# Controller_Board_Interface.net
KiCad netlist of a schematic drawn in Altium Designer
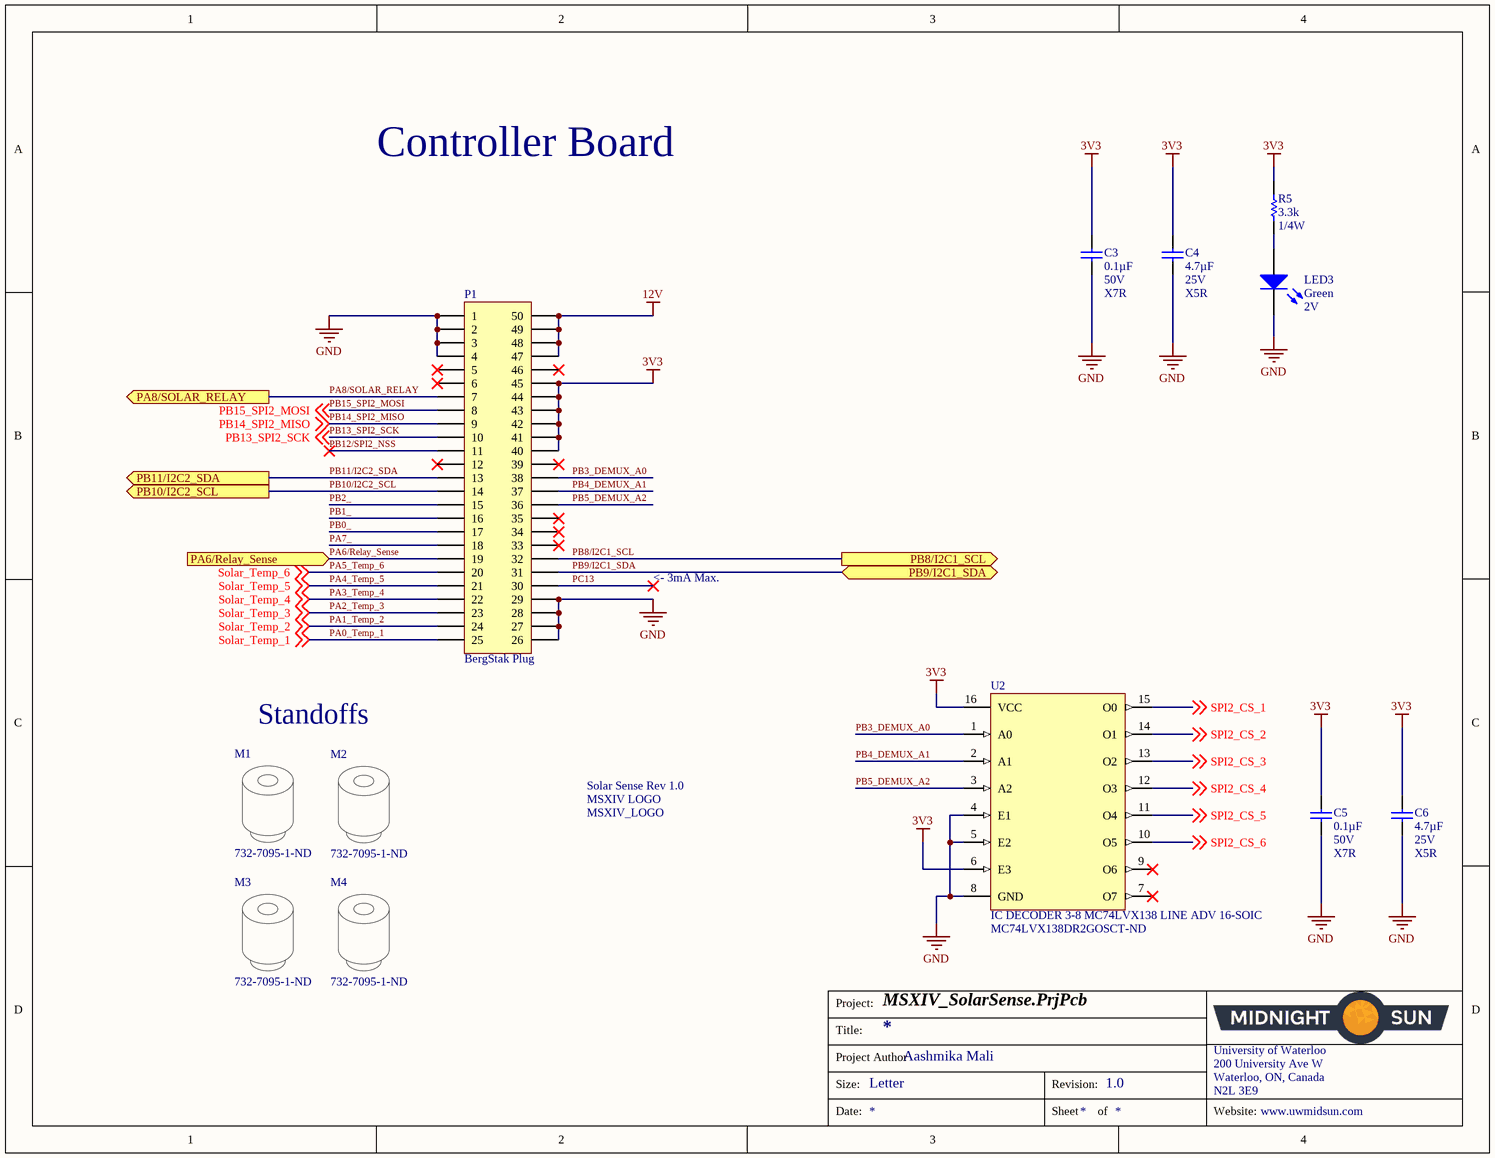
[diagram p0: Controller_Board_Interface.SchDoc]

(export (version "E")
  (design (tool "Eeschema 10.0.6"))
  (components
    (comp (ref "C3")
      (value "CAP CER 0.1UF 50V 10% X7R 0603")
      (footprint "CAP, 0603")
      (description "0.10µF ±10% 50V Ceramic Capacitor X7R 0603 (1608 Metric)")
      (fields
        (field (name "TOLERANCE") "±10%")
        (field (name "CAPACITANCE") "0.1µF")
        (field (name "VOLTAGE") "50V")
        (field (name "TEMPERATURE COEFFICIENT") "X7R")
      )
      (libsource (lib "Schematic Diagrams") (part "CAP CER 0.1UF 50V 10% X7R 0603"))
    )
    (comp (ref "C4")
      (value "CAP CER 4.7UF 25V 10% X5R 0603")
      (footprint "CAP, 0603")
      (description "4.7µF ±10% 25V Ceramic Capacitor X5R 0603 (1608 Metric)")
      (fields
        (field (name "TOLERANCE") "±10%")
        (field (name "CAPACITANCE") "4.7µF")
        (field (name "VOLTAGE") "25V")
        (field (name "TEMPERATURE COEFFICIENT") "X5R")
      )
      (libsource (lib "Schematic Diagrams") (part "CAP CER 4.7UF 25V 10% X5R 0603"))
    )
    (comp (ref "C5")
      (value "CAP CER 0.1UF 50V 10% X7R 0603")
      (footprint "CAP, 0603")
      (description "0.10µF ±10% 50V Ceramic Capacitor X7R 0603 (1608 Metric)")
      (fields
        (field (name "TOLERANCE") "±10%")
        (field (name "CAPACITANCE") "0.1µF")
        (field (name "VOLTAGE") "50V")
        (field (name "TEMPERATURE COEFFICIENT") "X7R")
      )
      (libsource (lib "Schematic Diagrams") (part "CAP CER 0.1UF 50V 10% X7R 0603"))
    )
    (comp (ref "C6")
      (value "CAP CER 4.7UF 25V 10% X5R 0603")
      (footprint "CAP, 0603")
      (description "4.7µF ±10% 25V Ceramic Capacitor X5R 0603 (1608 Metric)")
      (fields
        (field (name "TOLERANCE") "±10%")
        (field (name "CAPACITANCE") "4.7µF")
        (field (name "VOLTAGE") "25V")
        (field (name "TEMPERATURE COEFFICIENT") "X5R")
      )
      (libsource (lib "Schematic Diagrams") (part "CAP CER 4.7UF 25V 10% X5R 0603"))
    )
    (comp (ref "LED3")
      (value "LED GREEN CLEAR 2V 0603")
      (footprint "LED_0603")
      (description "Green 572nm LED Indication - Discrete 2V 0603 (1608 Metric)")
      (fields
        (field (name "MANUFACTURER") "Wurth Electronics Inc.")
        (field (name "MANUFACTURER PART NUMBER") "150060VS75000")
        (field (name "COLOR") "Green")
        (field (name "VOLTAGE - FORWARD (VF) (TYP)") "2V")
      )
      (libsource (lib "Schematic Diagrams") (part "LED GREEN CLEAR 2V 0603"))
    )
    (comp (ref "M1")
      (value "STANDOFF RND M2.5X0.45 STEEL 5MM")
      (footprint "M2.5 Standoff")
      (fields
        (field (name "MANUFACTURER") "Wurth Electronics")
        (field (name "MANUFACTURER PART NUMBER") "9774050151R")
        (field (name "SUPPLIER PART NUMBER 1") "732-7095-1-ND")
      )
      (libsource (lib "Schematic Diagrams") (part "STANDOFF RND M2.5X0.45 STEEL 5MM"))
    )
    (comp (ref "M2")
      (value "STANDOFF RND M2.5X0.45 STEEL 5MM")
      (footprint "M2.5 Standoff")
      (fields
        (field (name "MANUFACTURER") "Wurth Electronics")
        (field (name "MANUFACTURER PART NUMBER") "9774050151R")
        (field (name "SUPPLIER PART NUMBER 1") "732-7095-1-ND")
      )
      (libsource (lib "Schematic Diagrams") (part "STANDOFF RND M2.5X0.45 STEEL 5MM"))
    )
    (comp (ref "M3")
      (value "STANDOFF RND M2.5X0.45 STEEL 5MM")
      (footprint "M2.5 Standoff")
      (fields
        (field (name "MANUFACTURER") "Wurth Electronics")
        (field (name "MANUFACTURER PART NUMBER") "9774050151R")
        (field (name "SUPPLIER PART NUMBER 1") "732-7095-1-ND")
      )
      (libsource (lib "Schematic Diagrams") (part "STANDOFF RND M2.5X0.45 STEEL 5MM"))
    )
    (comp (ref "M4")
      (value "STANDOFF RND M2.5X0.45 STEEL 5MM")
      (footprint "M2.5 Standoff")
      (fields
        (field (name "MANUFACTURER") "Wurth Electronics")
        (field (name "MANUFACTURER PART NUMBER") "9774050151R")
        (field (name "SUPPLIER PART NUMBER 1") "732-7095-1-ND")
      )
      (libsource (lib "Schematic Diagrams") (part "STANDOFF RND M2.5X0.45 STEEL 5MM"))
    )
    (comp (ref "P1")
      (value "CONN 50POS Bergstak Plug 0.02\"")
      (footprint "CONN, Bergstak 50 Pos Plug")
      (description "50 Position Connector Plug, Outer Shroud Contacts Surface Mount Gold")
      (fields (field (name "SERIES") "BergStak Plug"))
      (libsource (lib "Schematic Diagrams") (part "CONN 50POS Bergstak Plug 0.02{dblquote}"))
    )
    (comp (ref "R5")
      (value "RES 3.3K OHM 1% 1/4W 0603")
      (footprint "RES, 0603")
      (fields
        (field (name "TOLERANCE") "±1%")
        (field (name "RESISTANCE") "3.3k")
        (field (name "POWER") "1/4W")
      )
      (libsource (lib "Schematic Diagrams") (part "RES 3.3K OHM 1% 1/4W 0603"))
    )
    (comp (ref "Solar Sense Rev 1.0")
      (value "MSXIV_LOGO")
      (footprint "MSXIV LOGO")
      (libsource (lib "Schematic Diagrams") (part "MSXIV_LOGO"))
    )
    (comp (ref "U2")
      (value "IC DECODER 3-8 MC74LVX138 LINE ADV 16-SOIC")
      (footprint "SOIC-16 CASE 751B-05 ISSUE K MC74LVX138")
      (description "Decoder/Demultiplexer 1 x 3:8 16-SOIC")
      (fields
        (field (name "MANUFACTURER") "ON Semiconductor")
        (field (name "MANUFACTURER PART NUMBER") "MC74LVX138DR2G")
        (field (name "SUPPLIER PART NUMBER 1") "MC74LVX138DR2GOSCT-ND")
      )
      (libsource (lib "Schematic Diagrams") (part "IC DECODER 3-8 MC74LVX138 LINE ADV 16-SOIC"))
    )
  )
  (nets
    (net (code "1") (name "/PA6{slash}Relay_Sense") (class "Default")
      (node (ref "P1") (pin "19") (pinfunction "19_19") (pintype "passive"))
    )
    (net (code "2") (name "/PA7_") (class "Default")
      (node (ref "P1") (pin "18") (pinfunction "18_18") (pintype "passive"))
    )
    (net (code "3") (name "/PA8{slash}SOLAR_RELAY") (class "Default")
      (node (ref "P1") (pin "7") (pinfunction "7_7") (pintype "passive"))
    )
    (net (code "4") (name "/PB0_") (class "Default")
      (node (ref "P1") (pin "17") (pinfunction "17_17") (pintype "passive"))
    )
    (net (code "5") (name "/PB1_") (class "Default")
      (node (ref "P1") (pin "16") (pinfunction "16_16") (pintype "passive"))
    )
    (net (code "6") (name "/PB2_") (class "Default")
      (node (ref "P1") (pin "15") (pinfunction "15_15") (pintype "passive"))
    )
    (net (code "7") (name "/PB3_DEMUX_A0") (class "Default")
      (node (ref "P1") (pin "38") (pinfunction "38_38") (pintype "passive"))
      (node (ref "U2") (pin "1") (pinfunction "A0_1") (pintype "input"))
    )
    (net (code "8") (name "/PB4_DEMUX_A1") (class "Default")
      (node (ref "P1") (pin "37") (pinfunction "37_37") (pintype "passive"))
      (node (ref "U2") (pin "2") (pinfunction "A1_2") (pintype "input"))
    )
    (net (code "9") (name "/PB5_DEMUX_A2") (class "Default")
      (node (ref "P1") (pin "36") (pinfunction "36_36") (pintype "passive"))
      (node (ref "U2") (pin "3") (pinfunction "A2_3") (pintype "input"))
    )
    (net (code "10") (name "/PB8{slash}I2C1_SCL") (class "Default")
      (node (ref "P1") (pin "32") (pinfunction "32_32") (pintype "passive"))
    )
    (net (code "11") (name "/PB9{slash}I2C1_SDA") (class "Default")
      (node (ref "P1") (pin "31") (pinfunction "31_31") (pintype "passive"))
    )
    (net (code "12") (name "/PB10{slash}I2C2_SCL") (class "Default")
      (node (ref "P1") (pin "14") (pinfunction "14_14") (pintype "passive"))
    )
    (net (code "13") (name "/PB11{slash}I2C2_SDA") (class "Default")
      (node (ref "P1") (pin "13") (pinfunction "13_13") (pintype "passive"))
    )
    (net (code "14") (name "/PB12{slash}SPI2_NSS") (class "Default")
      (node (ref "P1") (pin "11") (pinfunction "11_11") (pintype "passive+no_connect"))
    )
    (net (code "15") (name "/PC13") (class "Default")
      (node (ref "P1") (pin "30") (pinfunction "30_30") (pintype "passive+no_connect"))
    )
    (net (code "16") (name "3V3") (class "Default")
      (node (ref "C3") (pin "1") (pinfunction "1_1") (pintype "passive"))
      (node (ref "C4") (pin "1") (pinfunction "1_1") (pintype "passive"))
      (node (ref "C5") (pin "1") (pinfunction "1_1") (pintype "passive"))
      (node (ref "C6") (pin "1") (pinfunction "1_1") (pintype "passive"))
      (node (ref "P1") (pin "40") (pinfunction "40_40") (pintype "passive"))
      (node (ref "P1") (pin "41") (pinfunction "41_41") (pintype "passive"))
      (node (ref "P1") (pin "42") (pinfunction "42_42") (pintype "passive"))
      (node (ref "P1") (pin "43") (pinfunction "43_43") (pintype "passive"))
      (node (ref "P1") (pin "44") (pinfunction "44_44") (pintype "passive"))
      (node (ref "P1") (pin "45") (pinfunction "45_45") (pintype "passive"))
      (node (ref "R5") (pin "1") (pinfunction "1_1") (pintype "passive"))
      (node (ref "U2") (pin "16") (pinfunction "VCC_16") (pintype "power_in"))
      (node (ref "U2") (pin "6") (pinfunction "E3_6") (pintype "input"))
    )
    (net (code "17") (name "12V") (class "Default")
      (node (ref "P1") (pin "47") (pinfunction "47_47") (pintype "passive"))
      (node (ref "P1") (pin "48") (pinfunction "48_48") (pintype "passive"))
      (node (ref "P1") (pin "49") (pinfunction "49_49") (pintype "passive"))
      (node (ref "P1") (pin "50") (pinfunction "50_50") (pintype "passive"))
    )
    (net (code "18") (name "GND") (class "Default")
      (node (ref "C3") (pin "2") (pinfunction "2_2") (pintype "passive"))
      (node (ref "C4") (pin "2") (pinfunction "2_2") (pintype "passive"))
      (node (ref "C5") (pin "2") (pinfunction "2_2") (pintype "passive"))
      (node (ref "C6") (pin "2") (pinfunction "2_2") (pintype "passive"))
      (node (ref "LED3") (pin "2") (pinfunction "K_2") (pintype "passive"))
      (node (ref "P1") (pin "1") (pinfunction "1_1") (pintype "passive"))
      (node (ref "P1") (pin "2") (pinfunction "2_2") (pintype "passive"))
      (node (ref "P1") (pin "26") (pinfunction "26_26") (pintype "passive"))
      (node (ref "P1") (pin "27") (pinfunction "27_27") (pintype "passive"))
      (node (ref "P1") (pin "28") (pinfunction "28_28") (pintype "passive"))
      (node (ref "P1") (pin "29") (pinfunction "29_29") (pintype "passive"))
      (node (ref "P1") (pin "3") (pinfunction "3_3") (pintype "passive"))
      (node (ref "P1") (pin "4") (pinfunction "4_4") (pintype "passive"))
      (node (ref "U2") (pin "4") (pinfunction "E1_4") (pintype "input"))
      (node (ref "U2") (pin "5") (pinfunction "E2_5") (pintype "input"))
      (node (ref "U2") (pin "8") (pinfunction "GND_8") (pintype "power_in"))
    )
    (net (code "19") (name "Net-(LED3-A)") (class "Default")
      (node (ref "LED3") (pin "1") (pinfunction "A_1") (pintype "passive"))
      (node (ref "R5") (pin "2") (pinfunction "2_2") (pintype "passive"))
    )
    (net (code "20") (name "PB13_SPI2_SCK") (class "Default")
      (node (ref "P1") (pin "10") (pinfunction "10_10") (pintype "passive"))
    )
    (net (code "21") (name "PB14_SPI2_MISO") (class "Default")
      (node (ref "P1") (pin "9") (pinfunction "9_9") (pintype "passive"))
    )
    (net (code "22") (name "PB15_SPI2_MOSI") (class "Default")
      (node (ref "P1") (pin "8") (pinfunction "8_8") (pintype "passive"))
    )
    (net (code "23") (name "SPI2_CS_1") (class "Default")
      (node (ref "U2") (pin "15") (pinfunction "O0_15") (pintype "output"))
    )
    (net (code "24") (name "SPI2_CS_2") (class "Default")
      (node (ref "U2") (pin "14") (pinfunction "O1_14") (pintype "output"))
    )
    (net (code "25") (name "SPI2_CS_3") (class "Default")
      (node (ref "U2") (pin "13") (pinfunction "O2_13") (pintype "output"))
    )
    (net (code "26") (name "SPI2_CS_4") (class "Default")
      (node (ref "U2") (pin "12") (pinfunction "O3_12") (pintype "output"))
    )
    (net (code "27") (name "SPI2_CS_5") (class "Default")
      (node (ref "U2") (pin "11") (pinfunction "O4_11") (pintype "output"))
    )
    (net (code "28") (name "SPI2_CS_6") (class "Default")
      (node (ref "U2") (pin "10") (pinfunction "O5_10") (pintype "output"))
    )
    (net (code "29") (name "Solar_Temp_1") (class "Default")
      (node (ref "P1") (pin "25") (pinfunction "25_25") (pintype "passive"))
    )
    (net (code "30") (name "Solar_Temp_2") (class "Default")
      (node (ref "P1") (pin "24") (pinfunction "24_24") (pintype "passive"))
    )
    (net (code "31") (name "Solar_Temp_3") (class "Default")
      (node (ref "P1") (pin "23") (pinfunction "23_23") (pintype "passive"))
    )
    (net (code "32") (name "Solar_Temp_4") (class "Default")
      (node (ref "P1") (pin "22") (pinfunction "22_22") (pintype "passive"))
    )
    (net (code "33") (name "Solar_Temp_5") (class "Default")
      (node (ref "P1") (pin "21") (pinfunction "21_21") (pintype "passive"))
    )
    (net (code "34") (name "Solar_Temp_6") (class "Default")
      (node (ref "P1") (pin "20") (pinfunction "20_20") (pintype "passive"))
    )
    (net (code "35") (name "unconnected-(P1-Pad5)") (class "Default")
      (node (ref "P1") (pin "5") (pinfunction "5_5") (pintype "passive+no_connect"))
    )
    (net (code "36") (name "unconnected-(P1-Pad6)") (class "Default")
      (node (ref "P1") (pin "6") (pinfunction "6_6") (pintype "passive+no_connect"))
    )
    (net (code "37") (name "unconnected-(P1-Pad12)") (class "Default")
      (node (ref "P1") (pin "12") (pinfunction "12_12") (pintype "passive+no_connect"))
    )
    (net (code "38") (name "unconnected-(P1-Pad33)") (class "Default")
      (node (ref "P1") (pin "33") (pinfunction "33_33") (pintype "passive+no_connect"))
    )
    (net (code "39") (name "unconnected-(P1-Pad34)") (class "Default")
      (node (ref "P1") (pin "34") (pinfunction "34_34") (pintype "passive+no_connect"))
    )
    (net (code "40") (name "unconnected-(P1-Pad35)") (class "Default")
      (node (ref "P1") (pin "35") (pinfunction "35_35") (pintype "passive+no_connect"))
    )
    (net (code "41") (name "unconnected-(P1-Pad39)") (class "Default")
      (node (ref "P1") (pin "39") (pinfunction "39_39") (pintype "passive+no_connect"))
    )
    (net (code "42") (name "unconnected-(P1-Pad46)") (class "Default")
      (node (ref "P1") (pin "46") (pinfunction "46_46") (pintype "passive+no_connect"))
    )
    (net (code "43") (name "unconnected-(U2-O6-Pad9)") (class "Default")
      (node (ref "U2") (pin "9") (pinfunction "O6_9") (pintype "output+no_connect"))
    )
    (net (code "44") (name "unconnected-(U2-O7-Pad7)") (class "Default")
      (node (ref "U2") (pin "7") (pinfunction "O7_7") (pintype "output+no_connect"))
    )
  )
)
